# Fubarino_SD_v14t.net
KiCad netlist of a schematic drawn in EAGLE
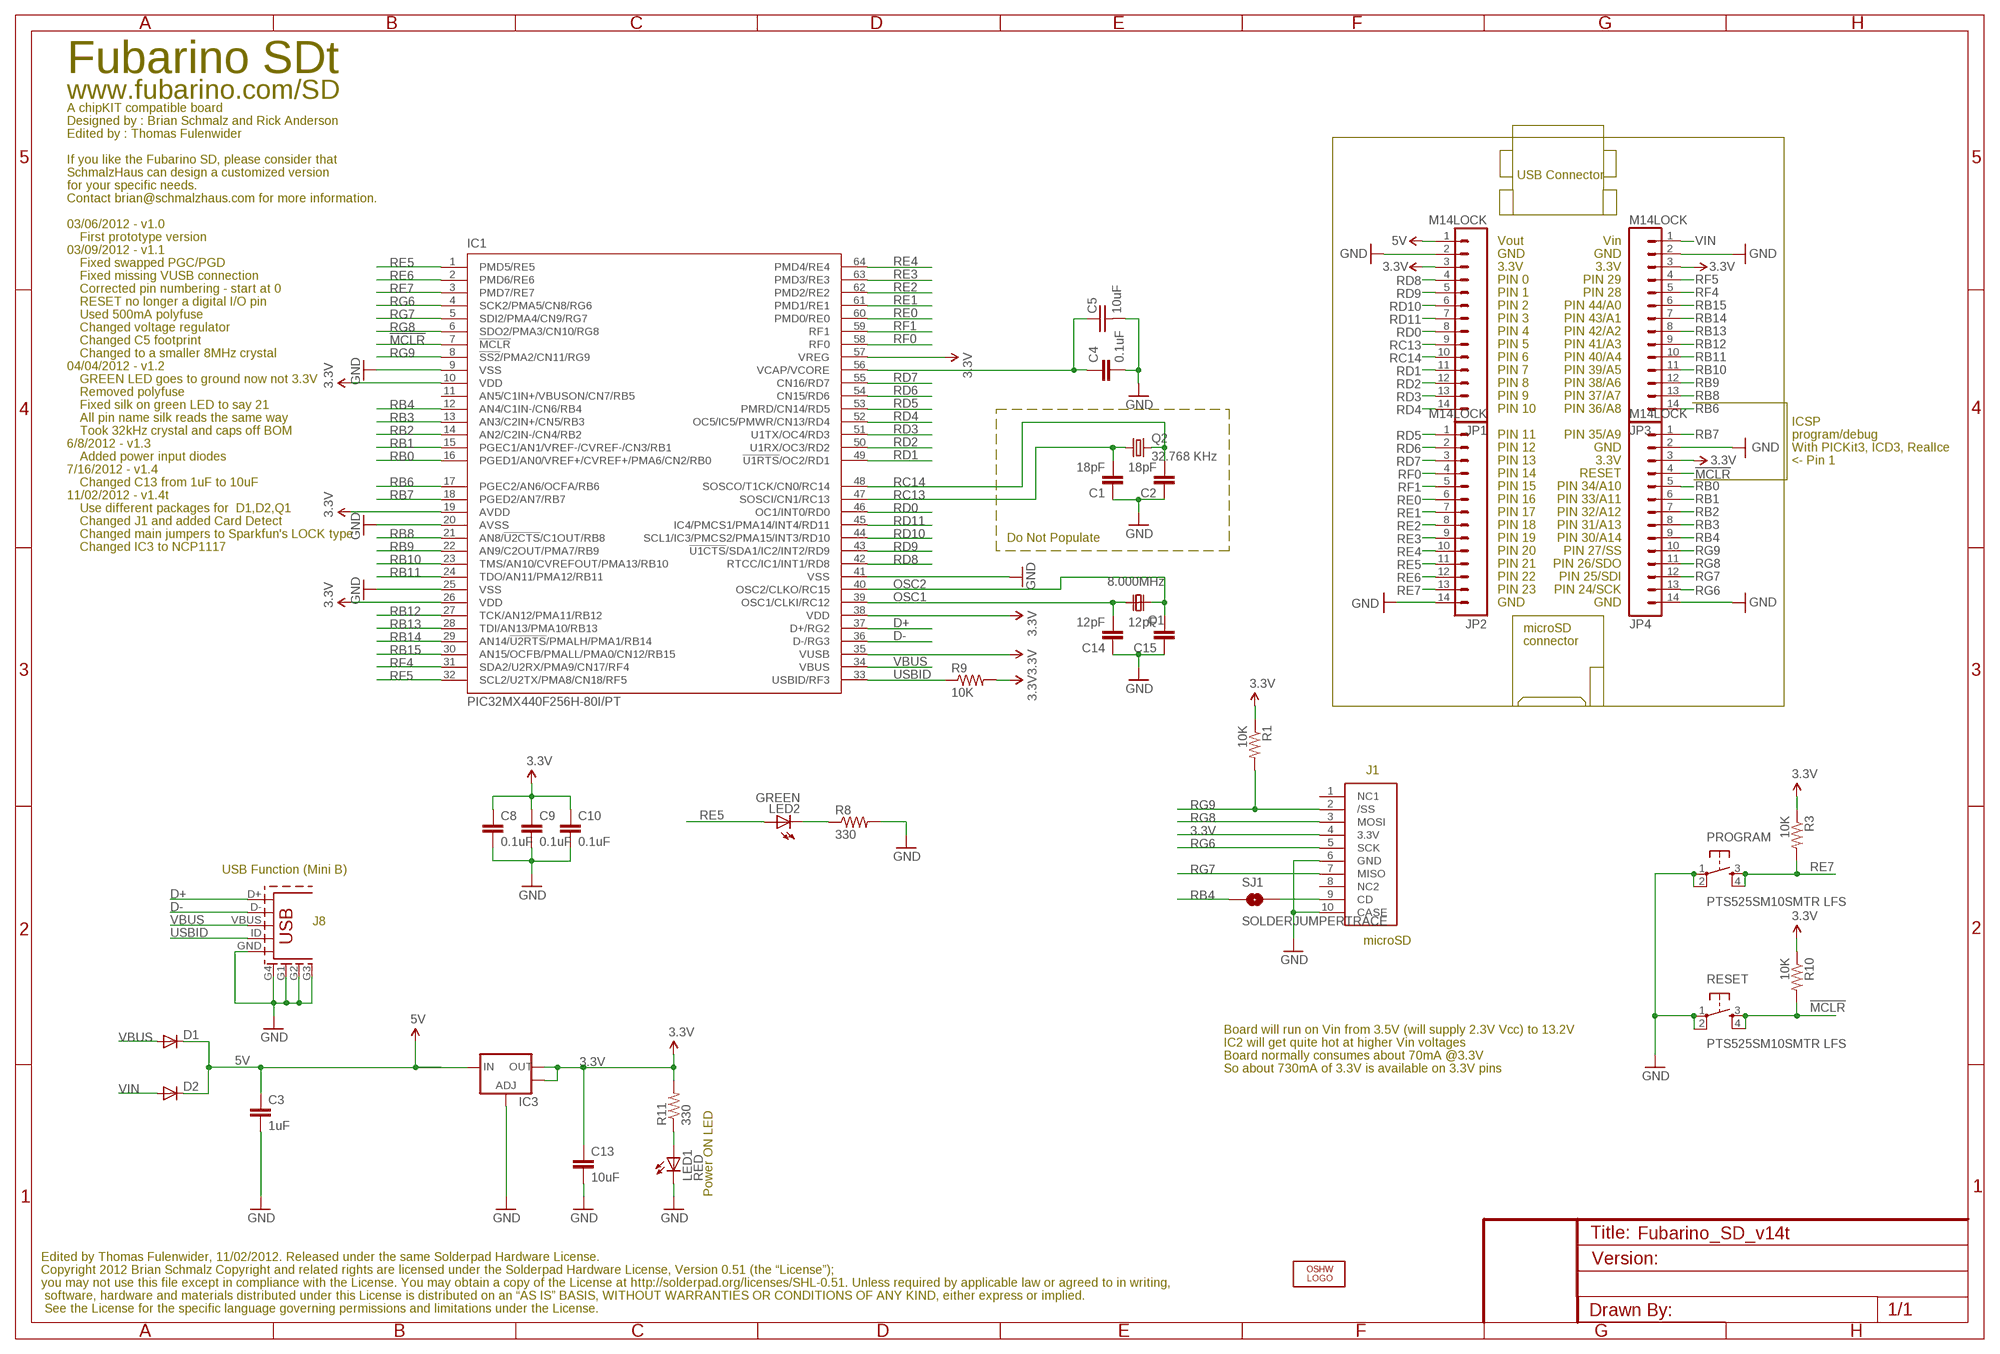
[diagram p0: schematic, sheet 1]

(export (version "E")
  (design (tool "Eeschema 10.0.6"))
  (components
    (comp (ref "C1")
      (value "18pF")
      (footprint "eagle-import:0603-CAP")
      (libsource (lib "eagle-import") (part "CAP0603-CAP"))
    )
    (comp (ref "C2")
      (value "18pF")
      (footprint "eagle-import:0603-CAP")
      (libsource (lib "eagle-import") (part "CAP0603-CAP"))
    )
    (comp (ref "C3")
      (value "1uF")
      (footprint "eagle-import:0603-CAP")
      (libsource (lib "eagle-import") (part "CAP0603-CAP"))
    )
    (comp (ref "C4")
      (value "0.1uF")
      (footprint "eagle-import:0603-CAP")
      (libsource (lib "eagle-import") (part "CAP0603-CAP"))
    )
    (comp (ref "C5")
      (value "10uF")
      (footprint "eagle-import:CAP_0805")
      (libsource (lib "eagle-import") (part "CAP0805"))
    )
    (comp (ref "C8")
      (value "0.1uF")
      (footprint "eagle-import:0603-CAP")
      (libsource (lib "eagle-import") (part "CAP0603-CAP"))
    )
    (comp (ref "C9")
      (value "0.1uF")
      (footprint "eagle-import:0603-CAP")
      (libsource (lib "eagle-import") (part "CAP0603-CAP"))
    )
    (comp (ref "C10")
      (value "0.1uF")
      (footprint "eagle-import:0603")
      (libsource (lib "eagle-import") (part "CAP0603"))
    )
    (comp (ref "C13")
      (value "10uF")
      (footprint "eagle-import:0805")
      (libsource (lib "eagle-import") (part "SparkFun02-20-08_CAP0805"))
    )
    (comp (ref "C14")
      (value "12pF")
      (footprint "eagle-import:0603-CAP")
      (libsource (lib "eagle-import") (part "CAP0603-CAP"))
    )
    (comp (ref "C15")
      (value "12pF")
      (footprint "eagle-import:0603-CAP")
      (libsource (lib "eagle-import") (part "CAP0603-CAP"))
    )
    (comp (ref "D1")
      (value "DIODE-SOD123")
      (footprint "eagle-import:SOD123")
      (libsource (lib "eagle-import") (part "DIODE-SOD123"))
    )
    (comp (ref "D2")
      (value "DIODE-SOD123")
      (footprint "eagle-import:SOD123")
      (libsource (lib "eagle-import") (part "DIODE-SOD123"))
    )
    (comp (ref "IC1")
      (value "PIC32MX440F256H-80I/PT")
      (footprint "eagle-import:TQFP64-10X10")
      (libsource (lib "eagle-import") (part "PIC32MX440F256H"))
    )
    (comp (ref "IC3")
      (value "V_REG_LM1117SOT223")
      (footprint "eagle-import:SOT223")
      (libsource (lib "eagle-import") (part "V_REG_LM1117SOT223"))
    )
    (comp (ref "J8")
      (value "UX60A-MB-5ST")
      (footprint "eagle-import:USB-MINIB")
      (libsource (lib "eagle-import") (part "USB_5PIN"))
    )
    (comp (ref "JP1")
      (value "M14LOCK")
      (footprint "eagle-import:1X14_LOCK")
      (libsource (lib "eagle-import") (part "M14LOCK"))
    )
    (comp (ref "JP2")
      (value "M14LOCK")
      (footprint "eagle-import:1X14_LOCK")
      (libsource (lib "eagle-import") (part "M14LOCK"))
    )
    (comp (ref "JP3")
      (value "M14LOCK")
      (footprint "eagle-import:1X14_LOCK")
      (libsource (lib "eagle-import") (part "M14LOCK"))
    )
    (comp (ref "JP4")
      (value "M14LOCK")
      (footprint "eagle-import:1X14_LOCK")
      (libsource (lib "eagle-import") (part "M14LOCK"))
    )
    (comp (ref "LED1")
      (value "RED")
      (footprint "eagle-import:LED-0603")
      (libsource (lib "eagle-import") (part "LED0603"))
    )
    (comp (ref "LED2")
      (value "GREEN")
      (footprint "eagle-import:LED-0603")
      (libsource (lib "eagle-import") (part "LED0603"))
    )
    (comp (ref "LOGO1")
      (value "OSHW_LOGO_8MILX0070-NT")
      (footprint "eagle-import:OSHW_8X70_NOTEXT")
      (libsource (lib "eagle-import") (part "OSHW_LOGO_8MILX0070-NT"))
    )
    (comp (ref "PROGRAM")
      (value "PTS525SM10SMTR LFS")
      (footprint "eagle-import:TACTILE_SWITCH_SMD")
      (libsource (lib "eagle-import") (part "TAC_SWITCHSMD"))
    )
    (comp (ref "Q1")
      (value "8.000MHz")
      (footprint "eagle-import:6035_METRIC")
      (libsource (lib "eagle-import") (part "METRIC_XTAL6035_METRIC"))
    )
    (comp (ref "Q2")
      (value "32.768 KHz")
      (footprint "eagle-import:TC26H")
      (libsource (lib "eagle-import") (part "CRYSTALTC26H"))
    )
    (comp (ref "R1")
      (value "10K")
      (footprint "eagle-import:0603-RES")
      (libsource (lib "eagle-import") (part "RESISTOR0603-RES"))
    )
    (comp (ref "R3")
      (value "10K")
      (footprint "eagle-import:0603-RES")
      (libsource (lib "eagle-import") (part "RESISTOR0603-RES"))
    )
    (comp (ref "R8")
      (value "330")
      (footprint "eagle-import:0603-RES")
      (libsource (lib "eagle-import") (part "RESISTOR0603-RES"))
    )
    (comp (ref "R9")
      (value "10K")
      (footprint "eagle-import:0603-RES")
      (libsource (lib "eagle-import") (part "RESISTOR0603-RES"))
    )
    (comp (ref "R10")
      (value "10K")
      (footprint "eagle-import:0603-RES")
      (libsource (lib "eagle-import") (part "RESISTOR0603-RES"))
    )
    (comp (ref "R11")
      (value "330")
      (footprint "eagle-import:0603-RES")
      (libsource (lib "eagle-import") (part "RESISTOR0603-RES"))
    )
    (comp (ref "RESET")
      (value "PTS525SM10SMTR LFS")
      (footprint "eagle-import:TACTILE_SWITCH_SMD")
      (libsource (lib "eagle-import") (part "TAC_SWITCHSMD"))
    )
    (comp (ref "SJ1")
      (value "SOLDERJUMPERTRACE")
      (footprint "eagle-import:SJ_2S-TRACE")
      (libsource (lib "eagle-import") (part "SOLDERJUMPERTRACE"))
    )
    (comp (ref "U$2")
      (value "SDCARDMICROSD1")
      (footprint "eagle-import:MICROSD")
      (libsource (lib "eagle-import") (part "SDCARDMICROSD1"))
    )
  )
  (nets
    (net (code "1") (name "/D+") (class "Default")
      (node (ref "IC1") (pin "37") (pinfunction "D+/RG2_37") (pintype "bidirectional"))
      (node (ref "J8") (pin "D+") (pinfunction "D+_D+") (pintype "bidirectional"))
    )
    (net (code "2") (name "/D-") (class "Default")
      (node (ref "IC1") (pin "36") (pinfunction "D-/RG3_36") (pintype "bidirectional"))
      (node (ref "J8") (pin "D-") (pinfunction "D-_D-") (pintype "bidirectional"))
    )
    (net (code "3") (name "/OSC1") (class "Default")
      (node (ref "C14") (pin "2") (pinfunction "2_2") (pintype "passive"))
      (node (ref "IC1") (pin "39") (pinfunction "OSC1/CLKI/RC12_39") (pintype "bidirectional"))
      (node (ref "Q1") (pin "P$1") (pinfunction "P$1_P$1") (pintype "bidirectional"))
    )
    (net (code "4") (name "/OSC2") (class "Default")
      (node (ref "C15") (pin "2") (pinfunction "2_2") (pintype "passive"))
      (node (ref "IC1") (pin "40") (pinfunction "OSC2/CLKO/RC15_40") (pintype "bidirectional"))
      (node (ref "Q1") (pin "P$2") (pinfunction "P$2_P$2") (pintype "bidirectional"))
    )
    (net (code "5") (name "/RB0") (class "Default")
      (node (ref "IC1") (pin "16") (pinfunction "PGED1/AN0/VREF+/CVREF+/PMA6/CN2/RB0_16") (pintype "bidirectional"))
      (node (ref "JP4") (pin "5") (pinfunction "5_5") (pintype "passive"))
    )
    (net (code "6") (name "/RB1") (class "Default")
      (node (ref "IC1") (pin "15") (pinfunction "PGEC1/AN1/VREF-/CVREF-/CN3/RB1_15") (pintype "bidirectional"))
      (node (ref "JP4") (pin "6") (pinfunction "6_6") (pintype "passive"))
    )
    (net (code "7") (name "/RB2") (class "Default")
      (node (ref "IC1") (pin "14") (pinfunction "AN2/C2IN-/CN4/RB2_14") (pintype "bidirectional"))
      (node (ref "JP4") (pin "7") (pinfunction "7_7") (pintype "passive"))
    )
    (net (code "8") (name "/RB3") (class "Default")
      (node (ref "IC1") (pin "13") (pinfunction "AN3/C2IN+/CN5/RB3_13") (pintype "bidirectional"))
      (node (ref "JP4") (pin "8") (pinfunction "8_8") (pintype "passive"))
    )
    (net (code "9") (name "/RB4") (class "Default")
      (node (ref "IC1") (pin "12") (pinfunction "AN4/C1IN-/CN6/RB4_12") (pintype "bidirectional"))
      (node (ref "JP4") (pin "9") (pinfunction "9_9") (pintype "passive"))
      (node (ref "SJ1") (pin "1") (pinfunction "1_1") (pintype "passive"))
    )
    (net (code "10") (name "/RB6") (class "Default")
      (node (ref "IC1") (pin "17") (pinfunction "PGEC2/AN6/OCFA/RB6_17") (pintype "bidirectional"))
      (node (ref "JP3") (pin "14") (pinfunction "14_14") (pintype "passive"))
    )
    (net (code "11") (name "/RB7") (class "Default")
      (node (ref "IC1") (pin "18") (pinfunction "PGED2/AN7/RB7_18") (pintype "bidirectional"))
      (node (ref "JP4") (pin "1") (pinfunction "1_1") (pintype "passive"))
    )
    (net (code "12") (name "/RB8") (class "Default")
      (node (ref "IC1") (pin "21") (pinfunction "AN8/~{U2CTS}/C1OUT/RB8_21") (pintype "bidirectional"))
      (node (ref "JP3") (pin "13") (pinfunction "13_13") (pintype "passive"))
    )
    (net (code "13") (name "/RB9") (class "Default")
      (node (ref "IC1") (pin "22") (pinfunction "AN9/C2OUT/PMA7/RB9_22") (pintype "bidirectional"))
      (node (ref "JP3") (pin "12") (pinfunction "12_12") (pintype "passive"))
    )
    (net (code "14") (name "/RB10") (class "Default")
      (node (ref "IC1") (pin "23") (pinfunction "TMS/AN10/CVREFOUT/PMA13/RB10_23") (pintype "input"))
      (node (ref "JP3") (pin "11") (pinfunction "11_11") (pintype "passive"))
    )
    (net (code "15") (name "/RB11") (class "Default")
      (node (ref "IC1") (pin "24") (pinfunction "TDO/AN11/PMA12/RB11_24") (pintype "output"))
      (node (ref "JP3") (pin "10") (pinfunction "10_10") (pintype "passive"))
    )
    (net (code "16") (name "/RB12") (class "Default")
      (node (ref "IC1") (pin "27") (pinfunction "TCK/AN12/PMA11/RB12_27") (pintype "input"))
      (node (ref "JP3") (pin "9") (pinfunction "9_9") (pintype "passive"))
    )
    (net (code "17") (name "/RB13") (class "Default")
      (node (ref "IC1") (pin "28") (pinfunction "TDI/AN13/PMA10/RB13_28") (pintype "input"))
      (node (ref "JP3") (pin "8") (pinfunction "8_8") (pintype "passive"))
    )
    (net (code "18") (name "/RB14") (class "Default")
      (node (ref "IC1") (pin "29") (pinfunction "AN14/~{U2RTS}/PMALH/PMA1/RB14_29") (pintype "bidirectional"))
      (node (ref "JP3") (pin "7") (pinfunction "7_7") (pintype "passive"))
    )
    (net (code "19") (name "/RB15") (class "Default")
      (node (ref "IC1") (pin "30") (pinfunction "AN15/OCFB/PMALL/PMA0/CN12/RB15_30") (pintype "bidirectional"))
      (node (ref "JP3") (pin "6") (pinfunction "6_6") (pintype "passive"))
    )
    (net (code "20") (name "/RC13") (class "Default")
      (node (ref "C1") (pin "2") (pinfunction "2_2") (pintype "passive"))
      (node (ref "IC1") (pin "47") (pinfunction "SOSCI/CN1/RC13_47") (pintype "bidirectional"))
      (node (ref "JP1") (pin "9") (pinfunction "9_9") (pintype "passive"))
      (node (ref "Q2") (pin "1") (pinfunction "1_1") (pintype "passive"))
    )
    (net (code "21") (name "/RC14") (class "Default")
      (node (ref "C2") (pin "2") (pinfunction "2_2") (pintype "passive"))
      (node (ref "IC1") (pin "48") (pinfunction "SOSCO/T1CK/CN0/RC14_48") (pintype "bidirectional"))
      (node (ref "JP1") (pin "10") (pinfunction "10_10") (pintype "passive"))
      (node (ref "Q2") (pin "2") (pinfunction "2_2") (pintype "passive"))
    )
    (net (code "22") (name "/RD0") (class "Default")
      (node (ref "IC1") (pin "46") (pinfunction "OC1/INT0/RD0_46") (pintype "bidirectional"))
      (node (ref "JP1") (pin "8") (pinfunction "8_8") (pintype "passive"))
    )
    (net (code "23") (name "/RD1") (class "Default")
      (node (ref "IC1") (pin "49") (pinfunction "~{U1RTS}/OC2/RD1_49") (pintype "bidirectional"))
      (node (ref "JP1") (pin "11") (pinfunction "11_11") (pintype "passive"))
    )
    (net (code "24") (name "/RD2") (class "Default")
      (node (ref "IC1") (pin "50") (pinfunction "U1RX/OC3/RD2_50") (pintype "bidirectional"))
      (node (ref "JP1") (pin "12") (pinfunction "12_12") (pintype "passive"))
    )
    (net (code "25") (name "/RD3") (class "Default")
      (node (ref "IC1") (pin "51") (pinfunction "U1TX/OC4/RD3_51") (pintype "bidirectional"))
      (node (ref "JP1") (pin "13") (pinfunction "13_13") (pintype "passive"))
    )
    (net (code "26") (name "/RD4") (class "Default")
      (node (ref "IC1") (pin "52") (pinfunction "OC5/IC5/PMWR/CN13/RD4_52") (pintype "bidirectional"))
      (node (ref "JP1") (pin "14") (pinfunction "14_14") (pintype "passive"))
    )
    (net (code "27") (name "/RD5") (class "Default")
      (node (ref "IC1") (pin "53") (pinfunction "PMRD/CN14/RD5_53") (pintype "bidirectional"))
      (node (ref "JP2") (pin "1") (pinfunction "1_1") (pintype "passive"))
    )
    (net (code "28") (name "/RD6") (class "Default")
      (node (ref "IC1") (pin "54") (pinfunction "CN15/RD6_54") (pintype "bidirectional"))
      (node (ref "JP2") (pin "2") (pinfunction "2_2") (pintype "passive"))
    )
    (net (code "29") (name "/RD7") (class "Default")
      (node (ref "IC1") (pin "55") (pinfunction "CN16/RD7_55") (pintype "bidirectional"))
      (node (ref "JP2") (pin "3") (pinfunction "3_3") (pintype "passive"))
    )
    (net (code "30") (name "/RD8") (class "Default")
      (node (ref "IC1") (pin "42") (pinfunction "RTCC/IC1/INT1/RD8_42") (pintype "bidirectional"))
      (node (ref "JP1") (pin "4") (pinfunction "4_4") (pintype "passive"))
    )
    (net (code "31") (name "/RD9") (class "Default")
      (node (ref "IC1") (pin "43") (pinfunction "~{U1CTS}/SDA1/IC2/INT2/RD9_43") (pintype "bidirectional"))
      (node (ref "JP1") (pin "5") (pinfunction "5_5") (pintype "passive"))
    )
    (net (code "32") (name "/RD10") (class "Default")
      (node (ref "IC1") (pin "44") (pinfunction "SCL1/IC3/PMCS2/PMA15/INT3/RD10_44") (pintype "bidirectional"))
      (node (ref "JP1") (pin "6") (pinfunction "6_6") (pintype "passive"))
    )
    (net (code "33") (name "/RD11") (class "Default")
      (node (ref "IC1") (pin "45") (pinfunction "IC4/PMCS1/PMA14/INT4/RD11_45") (pintype "bidirectional"))
      (node (ref "JP1") (pin "7") (pinfunction "7_7") (pintype "passive"))
    )
    (net (code "34") (name "/RE0") (class "Default")
      (node (ref "IC1") (pin "60") (pinfunction "PMD0/RE0_60") (pintype "bidirectional"))
      (node (ref "JP2") (pin "6") (pinfunction "6_6") (pintype "passive"))
    )
    (net (code "35") (name "/RE1") (class "Default")
      (node (ref "IC1") (pin "61") (pinfunction "PMD1/RE1_61") (pintype "bidirectional"))
      (node (ref "JP2") (pin "7") (pinfunction "7_7") (pintype "passive"))
    )
    (net (code "36") (name "/RE2") (class "Default")
      (node (ref "IC1") (pin "62") (pinfunction "PMD2/RE2_62") (pintype "bidirectional"))
      (node (ref "JP2") (pin "8") (pinfunction "8_8") (pintype "passive"))
    )
    (net (code "37") (name "/RE3") (class "Default")
      (node (ref "IC1") (pin "63") (pinfunction "PMD3/RE3_63") (pintype "bidirectional"))
      (node (ref "JP2") (pin "9") (pinfunction "9_9") (pintype "passive"))
    )
    (net (code "38") (name "/RE4") (class "Default")
      (node (ref "IC1") (pin "64") (pinfunction "PMD4/RE4_64") (pintype "bidirectional"))
      (node (ref "JP2") (pin "10") (pinfunction "10_10") (pintype "passive"))
    )
    (net (code "39") (name "/RE5") (class "Default")
      (node (ref "IC1") (pin "1") (pinfunction "PMD5/RE5_1") (pintype "bidirectional"))
      (node (ref "JP2") (pin "11") (pinfunction "11_11") (pintype "passive"))
      (node (ref "LED2") (pin "A") (pinfunction "A_A") (pintype "passive"))
    )
    (net (code "40") (name "/RE6") (class "Default")
      (node (ref "IC1") (pin "2") (pinfunction "PMD6/RE6_2") (pintype "bidirectional"))
      (node (ref "JP2") (pin "12") (pinfunction "12_12") (pintype "passive"))
    )
    (net (code "41") (name "/RE7") (class "Default")
      (node (ref "IC1") (pin "3") (pinfunction "PMD7/RE7_3") (pintype "bidirectional"))
      (node (ref "JP2") (pin "13") (pinfunction "13_13") (pintype "passive"))
      (node (ref "PROGRAM") (pin "3") (pinfunction "3_3") (pintype "passive"))
      (node (ref "PROGRAM") (pin "4") (pinfunction "4_4") (pintype "passive"))
      (node (ref "R3") (pin "2") (pinfunction "2_2") (pintype "passive"))
    )
    (net (code "42") (name "/RF0") (class "Default")
      (node (ref "IC1") (pin "58") (pinfunction "RF0_58") (pintype "bidirectional"))
      (node (ref "JP2") (pin "4") (pinfunction "4_4") (pintype "passive"))
    )
    (net (code "43") (name "/RF1") (class "Default")
      (node (ref "IC1") (pin "59") (pinfunction "RF1_59") (pintype "bidirectional"))
      (node (ref "JP2") (pin "5") (pinfunction "5_5") (pintype "passive"))
    )
    (net (code "44") (name "/RF4") (class "Default")
      (node (ref "IC1") (pin "31") (pinfunction "SDA2/U2RX/PMA9/CN17/RF4_31") (pintype "bidirectional"))
      (node (ref "JP3") (pin "5") (pinfunction "5_5") (pintype "passive"))
    )
    (net (code "45") (name "/RF5") (class "Default")
      (node (ref "IC1") (pin "32") (pinfunction "SCL2/U2TX/PMA8/CN18/RF5_32") (pintype "bidirectional"))
      (node (ref "JP3") (pin "4") (pinfunction "4_4") (pintype "passive"))
    )
    (net (code "46") (name "/RG6") (class "Default")
      (node (ref "IC1") (pin "4") (pinfunction "SCK2/PMA5/CN8/RG6_4") (pintype "bidirectional"))
      (node (ref "JP4") (pin "13") (pinfunction "13_13") (pintype "passive"))
      (node (ref "U$2") (pin "5") (pinfunction "SCK_5") (pintype "bidirectional"))
    )
    (net (code "47") (name "/RG7") (class "Default")
      (node (ref "IC1") (pin "5") (pinfunction "SDI2/PMA4/CN9/RG7_5") (pintype "bidirectional"))
      (node (ref "JP4") (pin "12") (pinfunction "12_12") (pintype "passive"))
      (node (ref "U$2") (pin "7") (pinfunction "MISO_7") (pintype "bidirectional"))
    )
    (net (code "48") (name "/RG8") (class "Default")
      (node (ref "IC1") (pin "6") (pinfunction "SDO2/PMA3/CN10/RG8_6") (pintype "bidirectional"))
      (node (ref "JP4") (pin "11") (pinfunction "11_11") (pintype "passive"))
      (node (ref "U$2") (pin "3") (pinfunction "MOSI_3") (pintype "bidirectional"))
    )
    (net (code "49") (name "/RG9") (class "Default")
      (node (ref "IC1") (pin "8") (pinfunction "~{SS2}/PMA2/CN11/RG9_8") (pintype "bidirectional"))
      (node (ref "JP4") (pin "10") (pinfunction "10_10") (pintype "passive"))
      (node (ref "R1") (pin "2") (pinfunction "2_2") (pintype "passive"))
      (node (ref "U$2") (pin "2") (pinfunction "/SS_2") (pintype "bidirectional"))
    )
    (net (code "50") (name "/USBID") (class "Default")
      (node (ref "IC1") (pin "33") (pinfunction "USBID/RF3_33") (pintype "bidirectional"))
      (node (ref "J8") (pin "ID") (pinfunction "USB_ID_ID") (pintype "bidirectional"))
      (node (ref "R9") (pin "1") (pinfunction "1_1") (pintype "passive"))
    )
    (net (code "51") (name "/VBUS") (class "Default")
      (node (ref "D1") (pin "A") (pinfunction "A_A") (pintype "passive"))
      (node (ref "IC1") (pin "34") (pinfunction "VBUS_34") (pintype "bidirectional"))
      (node (ref "J8") (pin "VBUS") (pinfunction "VBUS_VBUS") (pintype "bidirectional"))
    )
    (net (code "52") (name "/VIN") (class "Default")
      (node (ref "D2") (pin "A") (pinfunction "A_A") (pintype "passive"))
      (node (ref "JP3") (pin "1") (pinfunction "1_1") (pintype "passive"))
    )
    (net (code "53") (name "/~{MCLR}") (class "Default")
      (node (ref "IC1") (pin "7") (pinfunction "~{MCLR}_7") (pintype "input"))
      (node (ref "JP4") (pin "4") (pinfunction "4_4") (pintype "passive"))
      (node (ref "R10") (pin "2") (pinfunction "2_2") (pintype "passive"))
      (node (ref "RESET") (pin "3") (pinfunction "3_3") (pintype "passive"))
      (node (ref "RESET") (pin "4") (pinfunction "4_4") (pintype "passive"))
    )
    (net (code "54") (name "3.3V") (class "Default")
      (node (ref "C10") (pin "1") (pinfunction "1_1") (pintype "passive"))
      (node (ref "C13") (pin "1") (pinfunction "1_1") (pintype "passive"))
      (node (ref "C8") (pin "1") (pinfunction "1_1") (pintype "passive"))
      (node (ref "C9") (pin "1") (pinfunction "1_1") (pintype "passive"))
      (node (ref "IC1") (pin "10") (pinfunction "VDD_10") (pintype "power_in"))
      (node (ref "IC1") (pin "19") (pinfunction "AVDD_19") (pintype "power_in"))
      (node (ref "IC1") (pin "26") (pinfunction "VDD_26") (pintype "power_in"))
      (node (ref "IC1") (pin "35") (pinfunction "VUSB_35") (pintype "passive"))
      (node (ref "IC1") (pin "38") (pinfunction "VDD_38") (pintype "power_in"))
      (node (ref "IC1") (pin "57") (pinfunction "VREG_57") (pintype "passive"))
      (node (ref "IC3") (pin "2") (pinfunction "OUT_2") (pintype "output"))
      (node (ref "IC3") (pin "4") (pinfunction "OUT_4") (pintype "output"))
      (node (ref "JP1") (pin "3") (pinfunction "3_3") (pintype "passive"))
      (node (ref "JP3") (pin "3") (pinfunction "3_3") (pintype "passive"))
      (node (ref "JP4") (pin "3") (pinfunction "3_3") (pintype "passive"))
      (node (ref "R1") (pin "1") (pinfunction "1_1") (pintype "passive"))
      (node (ref "R10") (pin "1") (pinfunction "1_1") (pintype "passive"))
      (node (ref "R11") (pin "2") (pinfunction "2_2") (pintype "passive"))
      (node (ref "R3") (pin "1") (pinfunction "1_1") (pintype "passive"))
      (node (ref "R9") (pin "2") (pinfunction "2_2") (pintype "passive"))
      (node (ref "U$2") (pin "4") (pinfunction "3.3V_4") (pintype "bidirectional"))
    )
    (net (code "55") (name "5V") (class "Default")
      (node (ref "C3") (pin "1") (pinfunction "1_1") (pintype "passive"))
      (node (ref "D1") (pin "C") (pinfunction "C_C") (pintype "passive"))
      (node (ref "D2") (pin "C") (pinfunction "C_C") (pintype "passive"))
      (node (ref "IC3") (pin "3") (pinfunction "IN_3") (pintype "input"))
      (node (ref "JP1") (pin "1") (pinfunction "1_1") (pintype "passive"))
    )
    (net (code "56") (name "GND") (class "Default")
      (node (ref "C1") (pin "1") (pinfunction "1_1") (pintype "passive"))
      (node (ref "C10") (pin "2") (pinfunction "2_2") (pintype "passive"))
      (node (ref "C13") (pin "2") (pinfunction "2_2") (pintype "passive"))
      (node (ref "C14") (pin "1") (pinfunction "1_1") (pintype "passive"))
      (node (ref "C15") (pin "1") (pinfunction "1_1") (pintype "passive"))
      (node (ref "C2") (pin "1") (pinfunction "1_1") (pintype "passive"))
      (node (ref "C3") (pin "2") (pinfunction "2_2") (pintype "passive"))
      (node (ref "C4") (pin "2") (pinfunction "2_2") (pintype "passive"))
      (node (ref "C5") (pin "2") (pinfunction "2_2") (pintype "passive"))
      (node (ref "C8") (pin "2") (pinfunction "2_2") (pintype "passive"))
      (node (ref "C9") (pin "2") (pinfunction "2_2") (pintype "passive"))
      (node (ref "IC1") (pin "20") (pinfunction "AVSS_20") (pintype "power_in"))
      (node (ref "IC1") (pin "25") (pinfunction "VSS_25") (pintype "power_in"))
      (node (ref "IC1") (pin "41") (pinfunction "VSS_41") (pintype "power_in"))
      (node (ref "IC1") (pin "9") (pinfunction "VSS_9") (pintype "power_in"))
      (node (ref "IC3") (pin "1") (pinfunction "ADJ_1") (pintype "input"))
      (node (ref "J8") (pin "G1") (pinfunction "P$1_G1") (pintype "bidirectional"))
      (node (ref "J8") (pin "G2") (pinfunction "P$2_G2") (pintype "bidirectional"))
      (node (ref "J8") (pin "G3") (pinfunction "P$3_G3") (pintype "bidirectional"))
      (node (ref "J8") (pin "G4") (pinfunction "SHIELD_G4") (pintype "bidirectional"))
      (node (ref "J8") (pin "GND") (pinfunction "GND_GND") (pintype "bidirectional"))
      (node (ref "JP1") (pin "2") (pinfunction "2_2") (pintype "passive"))
      (node (ref "JP2") (pin "14") (pinfunction "14_14") (pintype "passive"))
      (node (ref "JP3") (pin "2") (pinfunction "2_2") (pintype "passive"))
      (node (ref "JP4") (pin "14") (pinfunction "14_14") (pintype "passive"))
      (node (ref "JP4") (pin "2") (pinfunction "2_2") (pintype "passive"))
      (node (ref "LED1") (pin "C") (pinfunction "C_C") (pintype "passive"))
      (node (ref "PROGRAM") (pin "1") (pinfunction "1_1") (pintype "passive"))
      (node (ref "PROGRAM") (pin "2") (pinfunction "2_2") (pintype "passive"))
      (node (ref "R8") (pin "2") (pinfunction "2_2") (pintype "passive"))
      (node (ref "RESET") (pin "1") (pinfunction "1_1") (pintype "passive"))
      (node (ref "RESET") (pin "2") (pinfunction "2_2") (pintype "passive"))
      (node (ref "U$2") (pin "10") (pinfunction "CASE_10") (pintype "bidirectional"))
      (node (ref "U$2") (pin "6") (pinfunction "GND_6") (pintype "bidirectional"))
    )
    (net (code "57") (name "Net-(IC1-VCAP{slash}VCORE)") (class "Default")
      (node (ref "C4") (pin "1") (pinfunction "1_1") (pintype "passive"))
      (node (ref "C5") (pin "1") (pinfunction "1_1") (pintype "passive"))
      (node (ref "IC1") (pin "56") (pinfunction "VCAP/VCORE_56") (pintype "power_in"))
    )
    (net (code "58") (name "Net-(LED1-PadA)") (class "Default")
      (node (ref "LED1") (pin "A") (pinfunction "A_A") (pintype "passive"))
      (node (ref "R11") (pin "1") (pinfunction "1_1") (pintype "passive"))
    )
    (net (code "59") (name "Net-(LED2-PadC)") (class "Default")
      (node (ref "LED2") (pin "C") (pinfunction "C_C") (pintype "passive"))
      (node (ref "R8") (pin "1") (pinfunction "1_1") (pintype "passive"))
    )
    (net (code "60") (name "Net-(U$2-CD)") (class "Default")
      (node (ref "SJ1") (pin "2") (pinfunction "2_2") (pintype "passive"))
      (node (ref "U$2") (pin "9") (pinfunction "CD_9") (pintype "bidirectional"))
    )
    (net (code "61") (name "unconnected-(IC1-AN5{slash}C1IN+{slash}VBUSON{slash}CN7{slash}RB5-Pad11)") (class "Default")
      (node (ref "IC1") (pin "11") (pinfunction "AN5/C1IN+/VBUSON/CN7/RB5_11") (pintype "bidirectional"))
    )
    (net (code "62") (name "unconnected-(U$2-NC1-Pad1)") (class "Default")
      (node (ref "U$2") (pin "1") (pinfunction "NC1_1") (pintype "bidirectional"))
    )
    (net (code "63") (name "unconnected-(U$2-NC2-Pad8)") (class "Default")
      (node (ref "U$2") (pin "8") (pinfunction "NC2_8") (pintype "bidirectional"))
    )
  )
)
